# SCH_BSPD_Main.net
KiCad netlist of a schematic drawn in Altium Designer
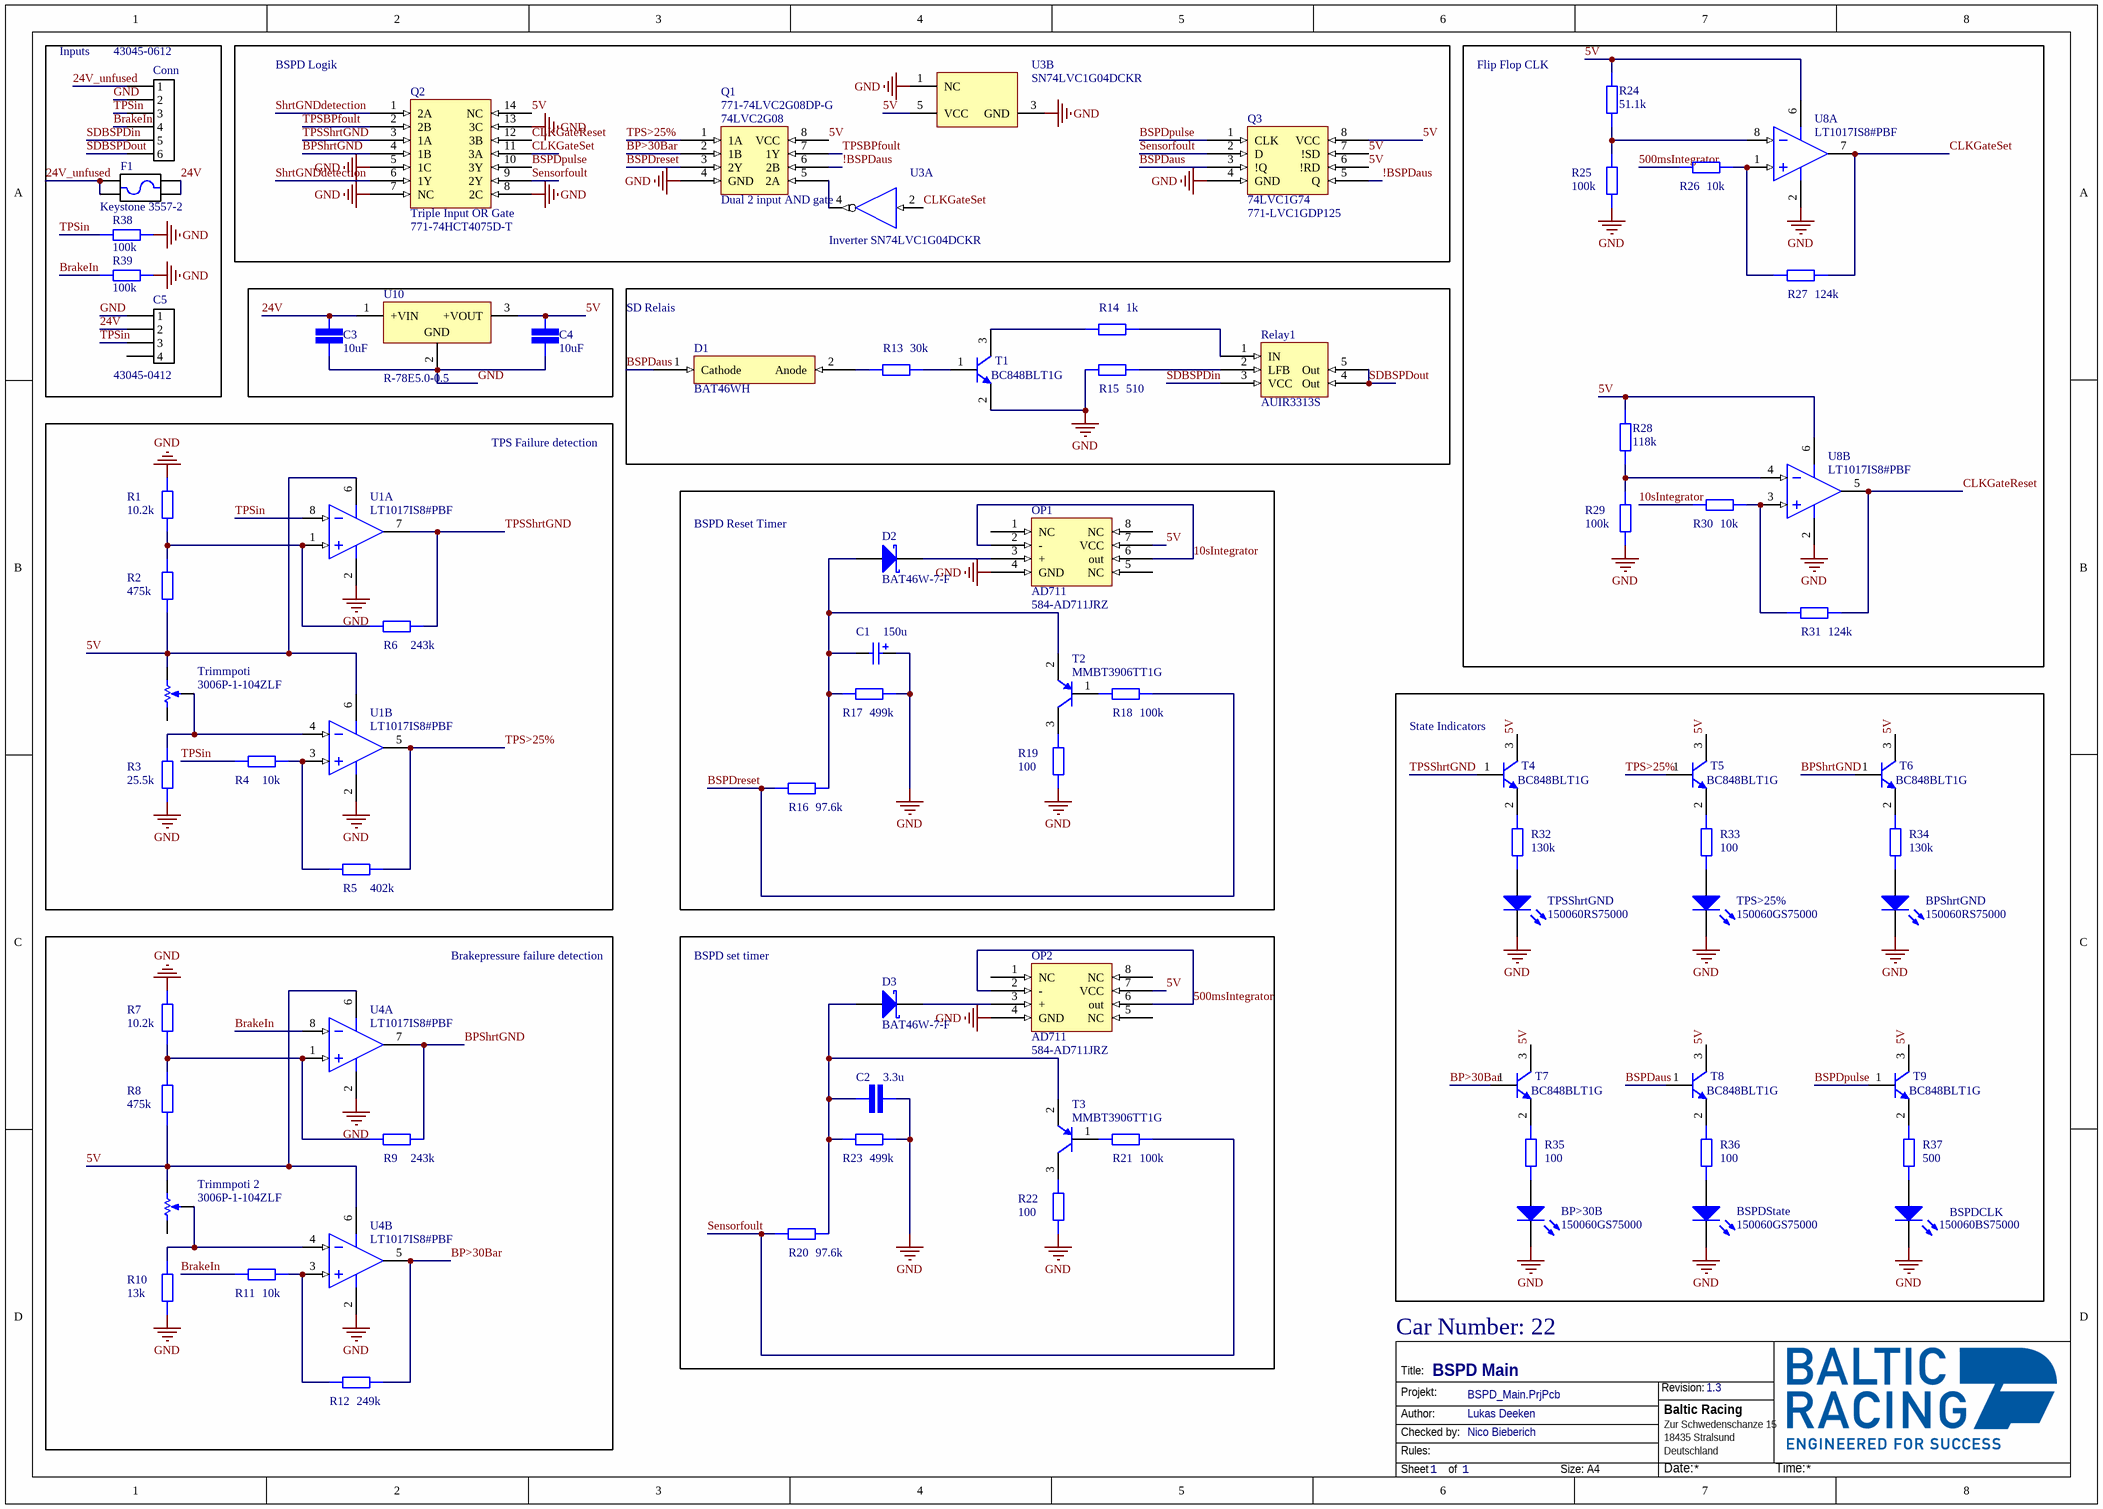
[diagram p0: SCH_BSPD_Main.SchDoc]

(export (version "E")
  (design (tool "Eeschema 10.0.6"))
  (components
    (comp (ref "BP>30B")
      (value "150060GS75000")
      (footprint "0603_A")
      (description "SMD mono-color Chip LED, WL-SMCW, Green")
      (fields (field (name "MANUFACTURER") "Wuerth Elektronik"))
      (libsource (lib "Altium Content Vault") (part "WE-LED_K1A2-2"))
    )
    (comp (ref "BPShrtGND")
      (value "150060RS75000")
      (footprint "0603_A")
      (description "SMD mono-color Chip LED, WL-SMCW, Red")
      (fields (field (name "MANUFACTURER") "Wuerth Elektronik"))
      (libsource (lib "Altium Content Vault") (part "WE-LED_K1A2-2"))
    )
    (comp (ref "BSPDCLK")
      (value "150060BS75000")
      (footprint "0603_A")
      (description "SMD mono-color Chip LED, WL-SMCW, Blue")
      (fields (field (name "MANUFACTURER") "Wuerth Elektronik"))
      (libsource (lib "Altium Content Vault") (part "WE-LED_K1A2-2"))
    )
    (comp (ref "BSPDState")
      (value "150060GS75000")
      (footprint "0603_A")
      (description "SMD mono-color Chip LED, WL-SMCW, Green")
      (fields (field (name "MANUFACTURER") "Wuerth Elektronik"))
      (libsource (lib "Altium Content Vault") (part "WE-LED_K1A2-2"))
    )
    (comp (ref "C1")
      (value "150u")
      (footprint "WCAP-PSLC_10x12.4")
      (description "WCAP-PSLC Aluminum Polymer Capacitors, size Ф10x12.4mm, 25V DC, 150uF")
      (fields (field (name "PART NUMBER") "875075561006") (field (name "PUBLISHER") "Wurth Elektronik"))
      (libsource (lib "ALTIUM-WCAP-PSLC-rev17b") (part "875075561006"))
    )
    (comp (ref "C2")
      (value "3.3u")
      (footprint "CAP 0603/1608")
      (description "Capacitor with multiple Footprints")
      (fields (field (name "VOLTAGE") "6.3V") (field (name "Comment") "SMD Capacitor"))
      (libsource (lib "") (part "SMD Capacitor_1"))
    )
    (comp (ref "C3")
      (value "10uF")
      (footprint "CAP 0805/2012")
      (description "Capacitor with multiple Footprints")
      (fields (field (name "VOLTAGE") "25V") (field (name "Comment") "SMD Capacitor"))
      (libsource (lib "Standardbauteile") (part "SMD Capacitor"))
    )
    (comp (ref "C4")
      (value "10uF")
      (footprint "CAP 0805/2012")
      (description "Capacitor with multiple Footprints")
      (fields (field (name "VOLTAGE") "6.3V") (field (name "Comment") "SMD Capacitor"))
      (libsource (lib "Standardbauteile") (part "SMD Capacitor"))
    )
    (comp (ref "C5")
      (value "43045-0412")
      (footprint "43045-0412")
      (description "Molex Micro-Fit 3.0 4-Pin\r\n600V\r\n8.5A")
      (libsource (lib "Standardbauteile") (part "MicroFit3.0 4-Pin"))
    )
    (comp (ref "Conn")
      (value "43045-0612")
      (footprint "43045-0612")
      (description "Molex Micro-Fit 3.0 6-Pin\r\n600V\r\n8.5A")
      (libsource (lib "Standardbauteile") (part "MicroFit3.0 6-Pin"))
    )
    (comp (ref "D1")
      (value "BAT46WH")
      (footprint "DIOM2715X18N")
      (libsource (lib "Integrated_LibraryLukas") (part "BAT46WH"))
    )
    (comp (ref "D2")
      (value "BAT46W-7-F")
      (footprint "DIOD-SOD-123-2_V")
      (description "Surface Mount Schottky Barrier Diode, 100 V, -55 to 125 degC, 2-Pin SOD123, RoHS, Tape and Reel")
      (fields (field (name "MANUFACTURER") "Diodes Inc"))
      (libsource (lib "Altium Content Vault") (part "DIOD-DSKY-A1K2-2"))
    )
    (comp (ref "D3")
      (value "BAT46W-7-F")
      (footprint "DIOD-SOD-123-2_V")
      (description "Surface Mount Schottky Barrier Diode, 100 V, -55 to 125 degC, 2-Pin SOD123, RoHS, Tape and Reel")
      (fields (field (name "MANUFACTURER") "Diodes Inc"))
      (libsource (lib "Altium Content Vault") (part "DIOD-DSKY-A1K2-2"))
    )
    (comp (ref "F1")
      (value "Keystone 3557-2")
      (footprint "Keystone 3557-2")
      (description "Keystone 3557-2\r\nFuse Holder")
      (libsource (lib "libNico") (part "Keystone 3557-2"))
    )
    (comp (ref "OP1")
      (value "AD711")
      (footprint "SOIC8; SOIC127P600X175-8N")
      (fields (field (name "SUPPLIER PART NUMBER 1") "584-AD711JRZ"))
      (libsource (lib "Integrated_LibraryLukas") (part "AD711"))
    )
    (comp (ref "OP2")
      (value "AD711")
      (footprint "SOIC8; SOIC127P600X175-8N")
      (fields (field (name "SUPPLIER PART NUMBER 1") "584-AD711JRZ"))
      (libsource (lib "Integrated_LibraryLukas") (part "AD711"))
    )
    (comp (ref "Q1")
      (value "Dual 2 input AND gate")
      (footprint "TSSOP8; TSOP65P400X110-8N")
      (fields (field (name "SUPPLIER PART NUMBER 1") "771-74LVC2G08DP-G"))
      (libsource (lib "Integrated_LibraryLukas") (part "74LVC2G08-Q100"))
    )
    (comp (ref "Q2")
      (value "Triple Input OR Gate")
      (footprint "SOIC14; SOIC127P600X175-14N")
      (fields (field (name "SUPPLIER PART NUMBER 1") "771-74HCT4075D-T"))
      (libsource (lib "Integrated_LibraryLukas") (part "74HCT4075D,653"))
    )
    (comp (ref "Q3")
      (value "74LVC1G74")
      (footprint "TSSOP8; TSOP65P400X110-8N")
      (fields (field (name "SUPPLIER PART NUMBER 1") "771-LVC1GDP125"))
      (libsource (lib "Integrated_LibraryLukas") (part "74LVC1G74"))
    )
    (comp (ref "R1")
      (value "10.2k")
      (footprint "STACKPOLE CSR0603")
      (description "Resistor with multiple footprints")
      (fields (field (name "Comment") "SMD Resistor"))
      (libsource (lib "Standardbauteile") (part "SMD Resistor"))
    )
    (comp (ref "R2")
      (value "475k")
      (footprint "STACKPOLE CSR0603")
      (description "Resistor with multiple footprints")
      (fields (field (name "Comment") "SMD Resistor"))
      (libsource (lib "Standardbauteile") (part "SMD Resistor"))
    )
    (comp (ref "R3")
      (value "25.5k")
      (footprint "STACKPOLE CSR0603")
      (description "Resistor with multiple footprints")
      (fields (field (name "Comment") "SMD Resistor"))
      (libsource (lib "Standardbauteile") (part "SMD Resistor"))
    )
    (comp (ref "R4")
      (value "10k")
      (footprint "STACKPOLE CSR0603")
      (description "Resistor with multiple footprints")
      (fields (field (name "Comment") "SMD Resistor"))
      (libsource (lib "Standardbauteile") (part "SMD Resistor"))
    )
    (comp (ref "R5")
      (value "402k")
      (footprint "STACKPOLE CSR0603")
      (description "Resistor with multiple footprints")
      (fields (field (name "Comment") "SMD Resistor"))
      (libsource (lib "Standardbauteile") (part "SMD Resistor"))
    )
    (comp (ref "R6")
      (value "243k")
      (footprint "STACKPOLE CSR0603")
      (description "Resistor with multiple footprints")
      (fields (field (name "Comment") "SMD Resistor"))
      (libsource (lib "Standardbauteile") (part "SMD Resistor"))
    )
    (comp (ref "R7")
      (value "10.2k")
      (footprint "STACKPOLE CSR0603")
      (description "Resistor with multiple footprints")
      (fields (field (name "Comment") "SMD Resistor"))
      (libsource (lib "Standardbauteile") (part "SMD Resistor"))
    )
    (comp (ref "R8")
      (value "475k")
      (footprint "STACKPOLE CSR0603")
      (description "Resistor with multiple footprints")
      (fields (field (name "Comment") "SMD Resistor"))
      (libsource (lib "Standardbauteile") (part "SMD Resistor"))
    )
    (comp (ref "R9")
      (value "243k")
      (footprint "STACKPOLE CSR0603")
      (description "Resistor with multiple footprints")
      (fields (field (name "Comment") "SMD Resistor"))
      (libsource (lib "Standardbauteile") (part "SMD Resistor"))
    )
    (comp (ref "R10")
      (value "13k")
      (footprint "STACKPOLE CSR0603")
      (description "Resistor with multiple footprints")
      (fields (field (name "Comment") "SMD Resistor"))
      (libsource (lib "Standardbauteile") (part "SMD Resistor"))
    )
    (comp (ref "R11")
      (value "10k")
      (footprint "STACKPOLE CSR0603")
      (description "Resistor with multiple footprints")
      (fields (field (name "Comment") "SMD Resistor"))
      (libsource (lib "Standardbauteile") (part "SMD Resistor"))
    )
    (comp (ref "R12")
      (value "249k")
      (footprint "STACKPOLE CSR0603")
      (description "Resistor with multiple footprints")
      (fields (field (name "Comment") "SMD Resistor"))
      (libsource (lib "Standardbauteile") (part "SMD Resistor"))
    )
    (comp (ref "R13")
      (value "30k")
      (footprint "STACKPOLE CSR0603")
      (description "Resistor with multiple footprints")
      (fields (field (name "Comment") "SMD Resistor"))
      (libsource (lib "Standardbauteile") (part "SMD Resistor"))
    )
    (comp (ref "R14")
      (value "1k")
      (footprint "STACKPOLE CSR0805")
      (description "Resistor with multiple footprints")
      (fields (field (name "Comment") "SMD Resistor"))
      (libsource (lib "Standardbauteile") (part "SMD Resistor"))
    )
    (comp (ref "R15")
      (value "510")
      (footprint "STACKPOLE CSR0603")
      (description "Resistor with multiple footprints")
      (fields (field (name "Comment") "SMD Resistor"))
      (libsource (lib "Standardbauteile") (part "SMD Resistor"))
    )
    (comp (ref "R16")
      (value "97.6k")
      (footprint "STACKPOLE CSR0603")
      (description "Resistor with multiple footprints")
      (fields (field (name "Comment") "SMD Resistor"))
      (libsource (lib "Standardbauteile") (part "SMD Resistor"))
    )
    (comp (ref "R17")
      (value "499k")
      (footprint "STACKPOLE CSR0603")
      (description "Resistor with multiple footprints")
      (fields (field (name "Comment") "SMD Resistor"))
      (libsource (lib "Standardbauteile") (part "SMD Resistor"))
    )
    (comp (ref "R18")
      (value "100k")
      (footprint "STACKPOLE CSR0603")
      (description "Resistor with multiple footprints")
      (fields (field (name "Comment") "SMD Resistor"))
      (libsource (lib "Standardbauteile") (part "SMD Resistor"))
    )
    (comp (ref "R19")
      (value "100")
      (footprint "STACKPOLE CSR0805")
      (description "Resistor with multiple footprints")
      (fields (field (name "Comment") "SMD Resistor"))
      (libsource (lib "Standardbauteile") (part "SMD Resistor"))
    )
    (comp (ref "R20")
      (value "97.6k")
      (footprint "STACKPOLE CSR0603")
      (description "Resistor with multiple footprints")
      (fields (field (name "Comment") "SMD Resistor"))
      (libsource (lib "Standardbauteile") (part "SMD Resistor"))
    )
    (comp (ref "R21")
      (value "100k")
      (footprint "STACKPOLE CSR0603")
      (description "Resistor with multiple footprints")
      (fields (field (name "Comment") "SMD Resistor"))
      (libsource (lib "Standardbauteile") (part "SMD Resistor"))
    )
    (comp (ref "R22")
      (value "100")
      (footprint "STACKPOLE CSR0805")
      (description "Resistor with multiple footprints")
      (fields (field (name "Comment") "SMD Resistor"))
      (libsource (lib "Standardbauteile") (part "SMD Resistor"))
    )
    (comp (ref "R23")
      (value "499k")
      (footprint "STACKPOLE CSR0603")
      (description "Resistor with multiple footprints")
      (fields (field (name "Comment") "SMD Resistor"))
      (libsource (lib "Standardbauteile") (part "SMD Resistor"))
    )
    (comp (ref "R24")
      (value "51.1k")
      (footprint "STACKPOLE CSR0603")
      (description "Resistor with multiple footprints")
      (fields (field (name "Comment") "SMD Resistor"))
      (libsource (lib "Standardbauteile") (part "SMD Resistor"))
    )
    (comp (ref "R25")
      (value "100k")
      (footprint "STACKPOLE CSR0603")
      (description "Resistor with multiple footprints")
      (fields (field (name "Comment") "SMD Resistor"))
      (libsource (lib "Standardbauteile") (part "SMD Resistor"))
    )
    (comp (ref "R26")
      (value "10k")
      (footprint "STACKPOLE CSR0603")
      (description "Resistor with multiple footprints")
      (fields (field (name "Comment") "SMD Resistor"))
      (libsource (lib "Standardbauteile") (part "SMD Resistor"))
    )
    (comp (ref "R27")
      (value "124k")
      (footprint "STACKPOLE CSR0603")
      (description "Resistor with multiple footprints")
      (fields (field (name "Comment") "SMD Resistor"))
      (libsource (lib "Standardbauteile") (part "SMD Resistor"))
    )
    (comp (ref "R28")
      (value "118k")
      (footprint "STACKPOLE CSR0603")
      (description "Resistor with multiple footprints")
      (fields (field (name "Comment") "SMD Resistor"))
      (libsource (lib "Standardbauteile") (part "SMD Resistor"))
    )
    (comp (ref "R29")
      (value "100k")
      (footprint "STACKPOLE CSR0603")
      (description "Resistor with multiple footprints")
      (fields (field (name "Comment") "SMD Resistor"))
      (libsource (lib "Standardbauteile") (part "SMD Resistor"))
    )
    (comp (ref "R30")
      (value "10k")
      (footprint "STACKPOLE CSR0603")
      (description "Resistor with multiple footprints")
      (fields (field (name "Comment") "SMD Resistor"))
      (libsource (lib "Standardbauteile") (part "SMD Resistor"))
    )
    (comp (ref "R31")
      (value "124k")
      (footprint "STACKPOLE CSR0603")
      (description "Resistor with multiple footprints")
      (fields (field (name "Comment") "SMD Resistor"))
      (libsource (lib "Standardbauteile") (part "SMD Resistor"))
    )
    (comp (ref "R32")
      (value "130k")
      (footprint "STACKPOLE CSR0603")
      (description "Resistor with multiple footprints")
      (fields (field (name "Comment") "SMD Resistor"))
      (libsource (lib "Standardbauteile") (part "SMD Resistor"))
    )
    (comp (ref "R33")
      (value "100")
      (footprint "STACKPOLE CSR0603")
      (description "Resistor with multiple footprints")
      (fields (field (name "Comment") "SMD Resistor"))
      (libsource (lib "Standardbauteile") (part "SMD Resistor"))
    )
    (comp (ref "R34")
      (value "130k")
      (footprint "STACKPOLE CSR0603")
      (description "Resistor with multiple footprints")
      (fields (field (name "Comment") "SMD Resistor"))
      (libsource (lib "Standardbauteile") (part "SMD Resistor"))
    )
    (comp (ref "R35")
      (value "100")
      (footprint "STACKPOLE CSR0603")
      (description "Resistor with multiple footprints")
      (fields (field (name "Comment") "SMD Resistor"))
      (libsource (lib "Standardbauteile") (part "SMD Resistor"))
    )
    (comp (ref "R36")
      (value "100")
      (footprint "STACKPOLE CSR0603")
      (description "Resistor with multiple footprints")
      (fields (field (name "Comment") "SMD Resistor"))
      (libsource (lib "Standardbauteile") (part "SMD Resistor"))
    )
    (comp (ref "R37")
      (value "500")
      (footprint "STACKPOLE CSR0603")
      (description "Resistor with multiple footprints")
      (fields (field (name "Comment") "SMD Resistor"))
      (libsource (lib "Standardbauteile") (part "SMD Resistor"))
    )
    (comp (ref "R38")
      (value "100k")
      (footprint "STACKPOLE CSR0603")
      (description "Resistor with multiple footprints")
      (fields (field (name "Comment") "SMD Resistor"))
      (libsource (lib "Standardbauteile") (part "SMD Resistor"))
    )
    (comp (ref "R39")
      (value "100k")
      (footprint "STACKPOLE CSR0603")
      (description "Resistor with multiple footprints")
      (fields (field (name "Comment") "SMD Resistor"))
      (libsource (lib "Standardbauteile") (part "SMD Resistor"))
    )
    (comp (ref "Relay1")
      (value "AUIR3313S")
      (footprint "D2PAK5 ;DPAK228P1524X483-5N")
      (libsource (lib "Integrated_LibraryLukas") (part "AUIR3313S"))
    )
    (comp (ref "T1")
      (value "BC848BLT1G")
      (footprint "ONSC-SOT-23-3-318-08_V")
      (description "General Purpose Transistor, NPN Silicon, 3-Pin SOT-23, Pb-Free, Tape and Reel")
      (fields (field (name "MANUFACTURER") "On Semiconductor"))
      (libsource (lib "Altium Content Vault") (part "ONSC-NPN-B1E2C3-3"))
    )
    (comp (ref "T2")
      (value "MMBT3906TT1G")
      (footprint "ONSC-SC-75-3-463-01_V")
      (description "General Purpose Transistor, PNP Silicon, 3-Pin SC-75, Pb-Free, Tape and Reel")
      (fields (field (name "MANUFACTURER") "On Semiconductor"))
      (libsource (lib "Altium Content Vault") (part "ONSC-PNP-B1E2C3-3"))
    )
    (comp (ref "T3")
      (value "MMBT3906TT1G")
      (footprint "ONSC-SC-75-3-463-01_V")
      (description "General Purpose Transistor, PNP Silicon, 3-Pin SC-75, Pb-Free, Tape and Reel")
      (fields (field (name "MANUFACTURER") "On Semiconductor"))
      (libsource (lib "Altium Content Vault") (part "ONSC-PNP-B1E2C3-3"))
    )
    (comp (ref "T4")
      (value "BC848BLT1G")
      (footprint "ONSC-SOT-23-3-318-08_V")
      (description "General Purpose Transistor, NPN Silicon, 3-Pin SOT-23, Pb-Free, Tape and Reel")
      (fields (field (name "MANUFACTURER") "On Semiconductor"))
      (libsource (lib "Altium Content Vault") (part "ONSC-NPN-B1E2C3-3"))
    )
    (comp (ref "T5")
      (value "BC848BLT1G")
      (footprint "ONSC-SOT-23-3-318-08_V")
      (description "General Purpose Transistor, NPN Silicon, 3-Pin SOT-23, Pb-Free, Tape and Reel")
      (fields (field (name "MANUFACTURER") "On Semiconductor"))
      (libsource (lib "Altium Content Vault") (part "ONSC-NPN-B1E2C3-3"))
    )
    (comp (ref "T6")
      (value "BC848BLT1G")
      (footprint "ONSC-SOT-23-3-318-08_V")
      (description "General Purpose Transistor, NPN Silicon, 3-Pin SOT-23, Pb-Free, Tape and Reel")
      (fields (field (name "MANUFACTURER") "On Semiconductor"))
      (libsource (lib "Altium Content Vault") (part "ONSC-NPN-B1E2C3-3"))
    )
    (comp (ref "T7")
      (value "BC848BLT1G")
      (footprint "ONSC-SOT-23-3-318-08_V")
      (description "General Purpose Transistor, NPN Silicon, 3-Pin SOT-23, Pb-Free, Tape and Reel")
      (fields (field (name "MANUFACTURER") "On Semiconductor"))
      (libsource (lib "Altium Content Vault") (part "ONSC-NPN-B1E2C3-3"))
    )
    (comp (ref "T8")
      (value "BC848BLT1G")
      (footprint "ONSC-SOT-23-3-318-08_V")
      (description "General Purpose Transistor, NPN Silicon, 3-Pin SOT-23, Pb-Free, Tape and Reel")
      (fields (field (name "MANUFACTURER") "On Semiconductor"))
      (libsource (lib "Altium Content Vault") (part "ONSC-NPN-B1E2C3-3"))
    )
    (comp (ref "T9")
      (value "BC848BLT1G")
      (footprint "ONSC-SOT-23-3-318-08_V")
      (description "General Purpose Transistor, NPN Silicon, 3-Pin SOT-23, Pb-Free, Tape and Reel")
      (fields (field (name "MANUFACTURER") "On Semiconductor"))
      (libsource (lib "Altium Content Vault") (part "ONSC-NPN-B1E2C3-3"))
    )
    (comp (ref "TPS>25%")
      (value "150060GS75000")
      (footprint "0603_A")
      (description "SMD mono-color Chip LED, WL-SMCW, Green")
      (fields (field (name "MANUFACTURER") "Wuerth Elektronik"))
      (libsource (lib "Altium Content Vault") (part "WE-LED_K1A2-2"))
    )
    (comp (ref "TPSShrtGND")
      (value "150060RS75000")
      (footprint "0603_A")
      (description "SMD mono-color Chip LED, WL-SMCW, Red")
      (fields (field (name "MANUFACTURER") "Wuerth Elektronik"))
      (libsource (lib "Altium Content Vault") (part "WE-LED_K1A2-2"))
    )
    (comp (ref "Trimmpoti")
      (value "3006P-1-104ZLF")
      (footprint "BOUR-3006P-3_V")
      (description "Trimming Potentiometer, 100K Ohm +/- 10%, -55 to 125 degC, 3-Pin 19.05 x 4.83 x 6.6 mm THD, RoHS")
      (fields (field (name "MANUFACTURER") "Bourns"))
      (libsource (lib "Altium Content Vault") (part "BOUR-3006P-3"))
    )
    (comp (ref "Trimmpoti 2")
      (value "3006P-1-104ZLF")
      (footprint "BOUR-3006P-3_V")
      (description "Trimming Potentiometer, 100K Ohm +/- 10%, -55 to 125 degC, 3-Pin 19.05 x 4.83 x 6.6 mm THD, RoHS")
      (fields (field (name "MANUFACTURER") "Bourns"))
      (libsource (lib "Altium Content Vault") (part "BOUR-3006P-3"))
    )
    (comp (ref "U1")
      (value "LT1017IS8#PBF")
      (footprint "LT-S8_N")
      (description "Micropower Comparator, 2 Channels, 1.2 to 40 V, -40 to +85 degC, 8-pin SOP (S8)")
      (fields (field (name "MANUFACTURER") "Linear Technology") (field (name "GENERIC PART NUMBER") "LT1017"))
      (libsource (lib "Altium Content Vault") (part "LT-LT1017-SO8"))
    )
    (comp (ref "U3")
      (value "Inverter SN74LVC1G04DCKR")
      (footprint "DCK0005A_N")
      (description "Single Inverter, DCK0005A, LARGE T&R")
      (fields
        (field (name "GENERIC PART NUMBER") "SN74LVC1G04")
        (field (name "MANUFACTURER") "Texas Instruments")
      )
      (libsource (lib "Altium Content Vault") (part "TI-SN74XXX1XX4-XX-5"))
    )
    (comp (ref "U4")
      (value "LT1017IS8#PBF")
      (footprint "LT-S8_N")
      (description "Micropower Comparator, 2 Channels, 1.2 to 40 V, -40 to +85 degC, 8-pin SOP (S8)")
      (fields (field (name "MANUFACTURER") "Linear Technology") (field (name "GENERIC PART NUMBER") "LT1017"))
      (libsource (lib "Altium Content Vault") (part "LT-LT1017-SO8"))
    )
    (comp (ref "U8")
      (value "LT1017IS8#PBF")
      (footprint "LT-S8_N")
      (description "Micropower Comparator, 2 Channels, 1.2 to 40 V, -40 to +85 degC, 8-pin SOP (S8)")
      (fields (field (name "MANUFACTURER") "Linear Technology") (field (name "GENERIC PART NUMBER") "LT1017"))
      (libsource (lib "Altium Content Vault") (part "LT-LT1017-SO8"))
    )
    (comp (ref "U10")
      (value "R-78E5.0-0.5")
      (footprint "REPO-R-78E-0.5-3_V")
      (description "DC/DC-Converter, 5 V Single Output, 500 mA, -40 to 85 degC, 3-Pin THD, RoHS, Tube")
      (fields (field (name "MANUFACTURER") "Recom Power"))
      (libsource (lib "Altium Content Vault") (part "REPO-R-78XX-3"))
    )
  )
  (nets
    (net (code "1") (name "/!BSPDaus") (class "Default")
      (node (ref "Q1") (pin "6") (pinfunction "2B_6") (pintype "input"))
      (node (ref "Q3") (pin "5") (pinfunction "Q_5") (pintype "input"))
    )
    (net (code "2") (name "/5V") (class "Default")
      (node (ref "C4") (pin "2") (pinfunction "2_2") (pintype "passive"))
      (node (ref "OP1") (pin "7") (pinfunction "VCC_7") (pintype "input"))
      (node (ref "OP2") (pin "7") (pinfunction "VCC_7") (pintype "input"))
      (node (ref "Q1") (pin "8") (pinfunction "VCC_8") (pintype "input"))
      (node (ref "Q2") (pin "14") (pinfunction "NC_14") (pintype "input"))
      (node (ref "Q3") (pin "6") (pinfunction "!RD_6") (pintype "input"))
      (node (ref "Q3") (pin "7") (pinfunction "!SD_7") (pintype "input"))
      (node (ref "Q3") (pin "8") (pinfunction "VCC_8") (pintype "input"))
      (node (ref "R2") (pin "2") (pinfunction "2_2") (pintype "passive"))
      (node (ref "R24") (pin "2") (pinfunction "2_2") (pintype "passive"))
      (node (ref "R28") (pin "2") (pinfunction "2_2") (pintype "passive"))
      (node (ref "R8") (pin "2") (pinfunction "2_2") (pintype "passive"))
      (node (ref "T4") (pin "3") (pinfunction "C_3") (pintype "passive"))
      (node (ref "T5") (pin "3") (pinfunction "C_3") (pintype "passive"))
      (node (ref "T6") (pin "3") (pinfunction "C_3") (pintype "passive"))
      (node (ref "T7") (pin "3") (pinfunction "C_3") (pintype "passive"))
      (node (ref "T8") (pin "3") (pinfunction "C_3") (pintype "passive"))
      (node (ref "T9") (pin "3") (pinfunction "C_3") (pintype "passive"))
      (node (ref "Trimmpoti") (pin "1") (pinfunction "CCW_1") (pintype "passive"))
      (node (ref "Trimmpoti 2") (pin "1") (pinfunction "CCW_1") (pintype "passive"))
      (node (ref "U1") (pin "6") (pinfunction "V+_6") (pintype "power_in"))
      (node (ref "U10") (pin "3") (pinfunction "+VOUT_3") (pintype "power_in"))
      (node (ref "U3") (pin "5") (pinfunction "VCC_5") (pintype "power_in"))
      (node (ref "U4") (pin "6") (pinfunction "V+_6") (pintype "power_in"))
      (node (ref "U8") (pin "6") (pinfunction "V+_6") (pintype "power_in"))
    )
    (net (code "3") (name "/10sIntegrator") (class "Default")
      (node (ref "OP1") (pin "2") (pinfunction "-_2") (pintype "input"))
      (node (ref "OP1") (pin "6") (pinfunction "out_6") (pintype "input"))
      (node (ref "R30") (pin "2") (pinfunction "2_2") (pintype "passive"))
    )
    (net (code "4") (name "/24V") (class "Default")
      (node (ref "C3") (pin "2") (pinfunction "2_2") (pintype "passive"))
      (node (ref "C5") (pin "2") (pinfunction "2_2") (pintype "passive"))
      (node (ref "F1") (pin "O1") (pinfunction "O1_O1") (pintype "passive"))
      (node (ref "F1") (pin "O2") (pinfunction "O2_O2") (pintype "passive"))
      (node (ref "U10") (pin "1") (pinfunction "+VIN_1") (pintype "power_in"))
    )
    (net (code "5") (name "/24V_unfused") (class "Default")
      (node (ref "Conn") (pin "1") (pinfunction "1_1") (pintype "passive"))
      (node (ref "F1") (pin "I1") (pinfunction "I1_I1") (pintype "passive"))
      (node (ref "F1") (pin "I2") (pinfunction "I2_I2") (pintype "passive"))
    )
    (net (code "6") (name "/500msIntegrator") (class "Default")
      (node (ref "OP2") (pin "2") (pinfunction "-_2") (pintype "input"))
      (node (ref "OP2") (pin "6") (pinfunction "out_6") (pintype "input"))
      (node (ref "R26") (pin "2") (pinfunction "2_2") (pintype "passive"))
    )
    (net (code "7") (name "/BP>30Bar") (class "Default")
      (node (ref "Q1") (pin "2") (pinfunction "1B_2") (pintype "input"))
      (node (ref "R12") (pin "2") (pinfunction "2_2") (pintype "passive"))
      (node (ref "T7") (pin "1") (pinfunction "B_1") (pintype "passive"))
      (node (ref "U4") (pin "5") (pinfunction "OUT_B_5") (pintype "open_collector"))
    )
    (net (code "8") (name "/BPShrtGND") (class "Default")
      (node (ref "Q2") (pin "4") (pinfunction "1B_4") (pintype "input"))
      (node (ref "R9") (pin "1") (pinfunction "1_1") (pintype "passive"))
      (node (ref "T6") (pin "1") (pinfunction "B_1") (pintype "passive"))
      (node (ref "U4") (pin "7") (pinfunction "OUT_A_7") (pintype "open_collector"))
    )
    (net (code "9") (name "/BSPDaus") (class "Default")
      (node (ref "D1") (pin "1") (pinfunction "Cathode_1") (pintype "input"))
      (node (ref "Q3") (pin "3") (pinfunction "!Q_3") (pintype "input"))
      (node (ref "T8") (pin "1") (pinfunction "B_1") (pintype "passive"))
    )
    (net (code "10") (name "/BSPDpulse") (class "Default")
      (node (ref "Q2") (pin "10") (pinfunction "3Y_10") (pintype "input"))
      (node (ref "Q3") (pin "1") (pinfunction "CLK_1") (pintype "input"))
      (node (ref "T9") (pin "1") (pinfunction "B_1") (pintype "passive"))
    )
    (net (code "11") (name "/BSPDreset") (class "Default")
      (node (ref "Q1") (pin "3") (pinfunction "2Y_3") (pintype "input"))
      (node (ref "R16") (pin "1") (pinfunction "1_1") (pintype "passive"))
      (node (ref "R18") (pin "2") (pinfunction "2_2") (pintype "passive"))
    )
    (net (code "12") (name "/BrakeIn") (class "Default")
      (node (ref "Conn") (pin "4") (pinfunction "4_4") (pintype "passive"))
      (node (ref "R11") (pin "2") (pinfunction "2_2") (pintype "passive"))
      (node (ref "R39") (pin "1") (pinfunction "1_1") (pintype "passive"))
      (node (ref "U4") (pin "8") (pinfunction "-IN_A_8") (pintype "input"))
    )
    (net (code "13") (name "/CLKGateReset") (class "Default")
      (node (ref "Q2") (pin "12") (pinfunction "3B_12") (pintype "input"))
      (node (ref "R31") (pin "2") (pinfunction "2_2") (pintype "passive"))
      (node (ref "U8") (pin "5") (pinfunction "OUT_B_5") (pintype "open_collector"))
    )
    (net (code "14") (name "/CLKGateSet") (class "Default")
      (node (ref "Q2") (pin "11") (pinfunction "3A_11") (pintype "input"))
      (node (ref "R27") (pin "2") (pinfunction "2_2") (pintype "passive"))
      (node (ref "U3") (pin "2") (pinfunction "A_2") (pintype "input"))
      (node (ref "U8") (pin "7") (pinfunction "OUT_A_7") (pintype "open_collector"))
    )
    (net (code "15") (name "/SDBSPDin") (class "Default")
      (node (ref "Conn") (pin "5") (pinfunction "5_5") (pintype "passive"))
      (node (ref "Relay1") (pin "3") (pinfunction "VCC_3") (pintype "input"))
    )
    (net (code "16") (name "/SDBSPDout") (class "Default")
      (node (ref "Conn") (pin "6") (pinfunction "6_6") (pintype "passive"))
      (node (ref "Relay1") (pin "4") (pinfunction "Out_4") (pintype "input"))
      (node (ref "Relay1") (pin "5") (pinfunction "Out_5") (pintype "input"))
    )
    (net (code "17") (name "/Sensorfoult") (class "Default")
      (node (ref "Q2") (pin "9") (pinfunction "2Y_9") (pintype "input"))
      (node (ref "Q3") (pin "2") (pinfunction "D_2") (pintype "input"))
      (node (ref "R20") (pin "1") (pinfunction "1_1") (pintype "passive"))
      (node (ref "R21") (pin "2") (pinfunction "2_2") (pintype "passive"))
    )
    (net (code "18") (name "/ShrtGNDdetection") (class "Default")
      (node (ref "Q2") (pin "1") (pinfunction "2A_1") (pintype "input"))
      (node (ref "Q2") (pin "6") (pinfunction "1Y_6") (pintype "input"))
    )
    (net (code "19") (name "/TPS>25%") (class "Default")
      (node (ref "Q1") (pin "1") (pinfunction "1A_1") (pintype "input"))
      (node (ref "R5") (pin "1") (pinfunction "1_1") (pintype "passive"))
      (node (ref "T5") (pin "1") (pinfunction "B_1") (pintype "passive"))
      (node (ref "U1") (pin "5") (pinfunction "OUT_B_5") (pintype "open_collector"))
    )
    (net (code "20") (name "/TPSBPfoult") (class "Default")
      (node (ref "Q1") (pin "7") (pinfunction "1Y_7") (pintype "input"))
      (node (ref "Q2") (pin "2") (pinfunction "2B_2") (pintype "input"))
    )
    (net (code "21") (name "/TPSShrtGND") (class "Default")
      (node (ref "Q2") (pin "3") (pinfunction "1A_3") (pintype "input"))
      (node (ref "R6") (pin "1") (pinfunction "1_1") (pintype "passive"))
      (node (ref "T4") (pin "1") (pinfunction "B_1") (pintype "passive"))
      (node (ref "U1") (pin "7") (pinfunction "OUT_A_7") (pintype "open_collector"))
    )
    (net (code "22") (name "/TPSin") (class "Default")
      (node (ref "C5") (pin "3") (pinfunction "3_3") (pintype "passive"))
      (node (ref "Conn") (pin "3") (pinfunction "3_3") (pintype "passive"))
      (node (ref "R38") (pin "1") (pinfunction "1_1") (pintype "passive"))
      (node (ref "R4") (pin "2") (pinfunction "2_2") (pintype "passive"))
      (node (ref "U1") (pin "8") (pinfunction "-IN_A_8") (pintype "input"))
    )
    (net (code "23") (name "GND") (class "Default")
      (node (ref "BP>30B") (pin "1") (pinfunction "K_1") (pintype "passive"))
      (node (ref "BPShrtGND") (pin "1") (pinfunction "K_1") (pintype "passive"))
      (node (ref "BSPDCLK") (pin "1") (pinfunction "K_1") (pintype "passive"))
      (node (ref "BSPDState") (pin "1") (pinfunction "K_1") (pintype "passive"))
      (node (ref "C1") (pin "1") (pinfunction "P_1") (pintype "passive"))
      (node (ref "C2") (pin "1") (pinfunction "1_1") (pintype "passive"))
      (node (ref "C3") (pin "1") (pinfunction "1_1") (pintype "passive"))
      (node (ref "C4") (pin "1") (pinfunction "1_1") (pintype "passive"))
      (node (ref "C5") (pin "1") (pinfunction "1_1") (pintype "passive"))
      (node (ref "Conn") (pin "2") (pinfunction "2_2") (pintype "passive"))
      (node (ref "OP1") (pin "4") (pinfunction "GND_4") (pintype "input"))
      (node (ref "OP2") (pin "4") (pinfunction "GND_4") (pintype "input"))
      (node (ref "Q1") (pin "4") (pinfunction "GND_4") (pintype "input"))
      (node (ref "Q2") (pin "13") (pinfunction "3C_13") (pintype "input"))
      (node (ref "Q2") (pin "5") (pinfunction "1C_5") (pintype "input"))
      (node (ref "Q2") (pin "7") (pinfunction "NC_7") (pintype "input"))
      (node (ref "Q2") (pin "8") (pinfunction "2C_8") (pintype "input"))
      (node (ref "Q3") (pin "4") (pinfunction "GND_4") (pintype "input"))
      (node (ref "R1") (pin "1") (pinfunction "1_1") (pintype "passive"))
      (node (ref "R10") (pin "2") (pinfunction "2_2") (pintype "passive"))
      (node (ref "R15") (pin "1") (pinfunction "1_1") (pintype "passive"))
      (node (ref "R17") (pin "2") (pinfunction "2_2") (pintype "passive"))
      (node (ref "R19") (pin "1") (pinfunction "1_1") (pintype "passive"))
      (node (ref "R22") (pin "1") (pinfunction "1_1") (pintype "passive"))
      (node (ref "R23") (pin "2") (pinfunction "2_2") (pintype "passive"))
      (node (ref "R25") (pin "2") (pinfunction "2_2") (pintype "passive"))
      (node (ref "R29") (pin "2") (pinfunction "2_2") (pintype "passive"))
      (node (ref "R3") (pin "2") (pinfunction "2_2") (pintype "passive"))
      (node (ref "R38") (pin "2") (pinfunction "2_2") (pintype "passive"))
      (node (ref "R39") (pin "2") (pinfunction "2_2") (pintype "passive"))
      (node (ref "R7") (pin "1") (pinfunction "1_1") (pintype "passive"))
      (node (ref "T1") (pin "2") (pinfunction "E_2") (pintype "passive"))
      (node (ref "TPS>25%") (pin "1") (pinfunction "K_1") (pintype "passive"))
      (node (ref "TPSShrtGND") (pin "1") (pinfunction "K_1") (pintype "passive"))
      (node (ref "U1") (pin "2") (pinfunction "V-_2") (pintype "power_in"))
      (node (ref "U10") (pin "2") (pinfunction "GND_2") (pintype "power_in"))
      (node (ref "U3") (pin "1") (pinfunction "NC_1") (pintype "passive"))
      (node (ref "U3") (pin "3") (pinfunction "GND_3") (pintype "power_in"))
      (node (ref "U4") (pin "2") (pinfunction "V-_2") (pintype "power_in"))
      (node (ref "U8") (pin "2") (pinfunction "V-_2") (pintype "power_in"))
    )
    (net (code "24") (name "Net-(BP>30B-A)") (class "Default")
      (node (ref "BP>30B") (pin "2") (pinfunction "A_2") (pintype "passive"))
      (node (ref "R35") (pin "1") (pinfunction "1_1") (pintype "passive"))
    )
    (net (code "25") (name "Net-(BPShrtGND-A)") (class "Default")
      (node (ref "BPShrtGND") (pin "2") (pinfunction "A_2") (pintype "passive"))
      (node (ref "R34") (pin "1") (pinfunction "1_1") (pintype "passive"))
    )
    (net (code "26") (name "Net-(BSPDCLK-A)") (class "Default")
      (node (ref "BSPDCLK") (pin "2") (pinfunction "A_2") (pintype "passive"))
      (node (ref "R37") (pin "1") (pinfunction "1_1") (pintype "passive"))
    )
    (net (code "27") (name "Net-(BSPDState-A)") (class "Default")
      (node (ref "BSPDState") (pin "2") (pinfunction "A_2") (pintype "passive"))
      (node (ref "R36") (pin "1") (pinfunction "1_1") (pintype "passive"))
    )
    (net (code "28") (name "Net-(C1-N)") (class "Default")
      (node (ref "C1") (pin "2") (pinfunction "N_2") (pintype "passive"))
      (node (ref "D2") (pin "1") (pinfunction "A_1") (pintype "passive"))
      (node (ref "R16") (pin "2") (pinfunction "2_2") (pintype "passive"))
      (node (ref "R17") (pin "1") (pinfunction "1_1") (pintype "passive"))
      (node (ref "T2") (pin "2") (pinfunction "E_2") (pintype "passive"))
    )
    (net (code "29") (name "Net-(D1-Anode)") (class "Default")
      (node (ref "D1") (pin "2") (pinfunction "Anode_2") (pintype "input"))
      (node (ref "R13") (pin "1") (pinfunction "1_1") (pintype "passive"))
    )
    (net (code "30") (name "Net-(D2-K)") (class "Default")
      (node (ref "D2") (pin "2") (pinfunction "K_2") (pintype "passive"))
      (node (ref "OP1") (pin "3") (pinfunction "+_3") (pintype "input"))
    )
    (net (code "31") (name "Net-(D3-A)") (class "Default")
      (node (ref "C2") (pin "2") (pinfunction "2_2") (pintype "passive"))
      (node (ref "D3") (pin "1") (pinfunction "A_1") (pintype "passive"))
      (node (ref "R20") (pin "2") (pinfunction "2_2") (pintype "passive"))
      (node (ref "R23") (pin "1") (pinfunction "1_1") (pintype "passive"))
      (node (ref "T3") (pin "2") (pinfunction "E_2") (pintype "passive"))
    )
    (net (code "32") (name "Net-(D3-K)") (class "Default")
      (node (ref "D3") (pin "2") (pinfunction "K_2") (pintype "passive"))
      (node (ref "OP2") (pin "3") (pinfunction "+_3") (pintype "input"))
    )
    (net (code "33") (name "Net-(Q1-2A)") (class "Default")
      (node (ref "Q1") (pin "5") (pinfunction "2A_5") (pintype "input"))
      (node (ref "U3") (pin "4") (pinfunction "Y_4") (pintype "output"))
    )
    (net (code "34") (name "Net-(Relay1-IN)") (class "Default")
      (node (ref "R14") (pin "2") (pinfunction "2_2") (pintype "passive"))
      (node (ref "Relay1") (pin "1") (pinfunction "IN_1") (pintype "input"))
    )
    (net (code "35") (name "Net-(Relay1-LFB)") (class "Default")
      (node (ref "R15") (pin "2") (pinfunction "2_2") (pintype "passive"))
      (node (ref "Relay1") (pin "2") (pinfunction "LFB_2") (pintype "input"))
    )
    (net (code "36") (name "Net-(T1-B)") (class "Default")
      (node (ref "R13") (pin "2") (pinfunction "2_2") (pintype "passive"))
      (node (ref "T1") (pin "1") (pinfunction "B_1") (pintype "passive"))
    )
    (net (code "37") (name "Net-(T1-C)") (class "Default")
      (node (ref "R14") (pin "1") (pinfunction "1_1") (pintype "passive"))
      (node (ref "T1") (pin "3") (pinfunction "C_3") (pintype "passive"))
    )
    (net (code "38") (name "Net-(T2-B)") (class "Default")
      (node (ref "R18") (pin "1") (pinfunction "1_1") (pintype "passive"))
      (node (ref "T2") (pin "1") (pinfunction "B_1") (pintype "passive"))
    )
    (net (code "39") (name "Net-(T2-C)") (class "Default")
      (node (ref "R19") (pin "2") (pinfunction "2_2") (pintype "passive"))
      (node (ref "T2") (pin "3") (pinfunction "C_3") (pintype "passive"))
    )
    (net (code "40") (name "Net-(T3-B)") (class "Default")
      (node (ref "R21") (pin "1") (pinfunction "1_1") (pintype "passive"))
      (node (ref "T3") (pin "1") (pinfunction "B_1") (pintype "passive"))
    )
    (net (code "41") (name "Net-(T3-C)") (class "Default")
      (node (ref "R22") (pin "2") (pinfunction "2_2") (pintype "passive"))
      (node (ref "T3") (pin "3") (pinfunction "C_3") (pintype "passive"))
    )
    (net (code "42") (name "Net-(T4-E)") (class "Default")
      (node (ref "R32") (pin "2") (pinfunction "2_2") (pintype "passive"))
      (node (ref "T4") (pin "2") (pinfunction "E_2") (pintype "passive"))
    )
    (net (code "43") (name "Net-(T5-E)") (class "Default")
      (node (ref "R33") (pin "2") (pinfunction "2_2") (pintype "passive"))
      (node (ref "T5") (pin "2") (pinfunction "E_2") (pintype "passive"))
    )
    (net (code "44") (name "Net-(T6-E)") (class "Default")
      (node (ref "R34") (pin "2") (pinfunction "2_2") (pintype "passive"))
      (node (ref "T6") (pin "2") (pinfunction "E_2") (pintype "passive"))
    )
    (net (code "45") (name "Net-(T7-E)") (class "Default")
      (node (ref "R35") (pin "2") (pinfunction "2_2") (pintype "passive"))
      (node (ref "T7") (pin "2") (pinfunction "E_2") (pintype "passive"))
    )
    (net (code "46") (name "Net-(T8-E)") (class "Default")
      (node (ref "R36") (pin "2") (pinfunction "2_2") (pintype "passive"))
      (node (ref "T8") (pin "2") (pinfunction "E_2") (pintype "passive"))
    )
    (net (code "47") (name "Net-(T9-E)") (class "Default")
      (node (ref "R37") (pin "2") (pinfunction "2_2") (pintype "passive"))
      (node (ref "T9") (pin "2") (pinfunction "E_2") (pintype "passive"))
    )
    (net (code "48") (name "Net-(TPS>25%-A)") (class "Default")
      (node (ref "R33") (pin "1") (pinfunction "1_1") (pintype "passive"))
      (node (ref "TPS>25%") (pin "2") (pinfunction "A_2") (pintype "passive"))
    )
    (net (code "49") (name "Net-(TPSShrtGND-A)") (class "Default")
      (node (ref "R32") (pin "1") (pinfunction "1_1") (pintype "passive"))
      (node (ref "TPSShrtGND") (pin "2") (pinfunction "A_2") (pintype "passive"))
    )
    (net (code "50") (name "Net-(Trimmpoti 2-WIPER)") (class "Default")
      (node (ref "R10") (pin "1") (pinfunction "1_1") (pintype "passive"))
      (node (ref "Trimmpoti 2") (pin "2") (pinfunction "WIPER_2") (pintype "passive"))
      (node (ref "U4") (pin "4") (pinfunction "-IN_B_4") (pintype "input"))
    )
    (net (code "51") (name "Net-(Trimmpoti-WIPER)") (class "Default")
      (node (ref "R3") (pin "1") (pinfunction "1_1") (pintype "passive"))
      (node (ref "Trimmpoti") (pin "2") (pinfunction "WIPER_2") (pintype "passive"))
      (node (ref "U1") (pin "4") (pinfunction "-IN_B_4") (pintype "input"))
    )
    (net (code "52") (name "Net-(U1A-+IN_A)") (class "Default")
      (node (ref "R1") (pin "2") (pinfunction "2_2") (pintype "passive"))
      (node (ref "R2") (pin "1") (pinfunction "1_1") (pintype "passive"))
      (node (ref "R6") (pin "2") (pinfunction "2_2") (pintype "passive"))
      (node (ref "U1") (pin "1") (pinfunction "+IN_A_1") (pintype "input"))
    )
    (net (code "53") (name "Net-(U1B-+IN_B)") (class "Default")
      (node (ref "R4") (pin "1") (pinfunction "1_1") (pintype "passive"))
      (node (ref "R5") (pin "2") (pinfunction "2_2") (pintype "passive"))
      (node (ref "U1") (pin "3") (pinfunction "+IN_B_3") (pintype "input"))
    )
    (net (code "54") (name "Net-(U4A-+IN_A)") (class "Default")
      (node (ref "R7") (pin "2") (pinfunction "2_2") (pintype "passive"))
      (node (ref "R8") (pin "1") (pinfunction "1_1") (pintype "passive"))
      (node (ref "R9") (pin "2") (pinfunction "2_2") (pintype "passive"))
      (node (ref "U4") (pin "1") (pinfunction "+IN_A_1") (pintype "input"))
    )
    (net (code "55") (name "Net-(U4B-+IN_B)") (class "Default")
      (node (ref "R11") (pin "1") (pinfunction "1_1") (pintype "passive"))
      (node (ref "R12") (pin "1") (pinfunction "1_1") (pintype "passive"))
      (node (ref "U4") (pin "3") (pinfunction "+IN_B_3") (pintype "input"))
    )
    (net (code "56") (name "Net-(U8A-+IN_A)") (class "Default")
      (node (ref "R26") (pin "1") (pinfunction "1_1") (pintype "passive"))
      (node (ref "R27") (pin "1") (pinfunction "1_1") (pintype "passive"))
      (node (ref "U8") (pin "1") (pinfunction "+IN_A_1") (pintype "input"))
    )
    (net (code "57") (name "Net-(U8A--IN_A)") (class "Default")
      (node (ref "R24") (pin "1") (pinfunction "1_1") (pintype "passive"))
      (node (ref "R25") (pin "1") (pinfunction "1_1") (pintype "passive"))
      (node (ref "U8") (pin "8") (pinfunction "-IN_A_8") (pintype "input"))
    )
    (net (code "58") (name "Net-(U8B-+IN_B)") (class "Default")
      (node (ref "R30") (pin "1") (pinfunction "1_1") (pintype "passive"))
      (node (ref "R31") (pin "1") (pinfunction "1_1") (pintype "passive"))
      (node (ref "U8") (pin "3") (pinfunction "+IN_B_3") (pintype "input"))
    )
    (net (code "59") (name "Net-(U8B--IN_B)") (class "Default")
      (node (ref "R28") (pin "1") (pinfunction "1_1") (pintype "passive"))
      (node (ref "R29") (pin "1") (pinfunction "1_1") (pintype "passive"))
      (node (ref "U8") (pin "4") (pinfunction "-IN_B_4") (pintype "input"))
    )
    (net (code "60") (name "unconnected-(C5-Pad4)") (class "Default")
      (node (ref "C5") (pin "4") (pinfunction "4_4") (pintype "passive"))
    )
    (net (code "61") (name "unconnected-(OP1-NC-Pad1)") (class "Default")
      (node (ref "OP1") (pin "1") (pinfunction "NC_1") (pintype "input"))
    )
    (net (code "62") (name "unconnected-(OP1-NC-Pad5)") (class "Default")
      (node (ref "OP1") (pin "5") (pinfunction "NC_5") (pintype "input"))
    )
    (net (code "63") (name "unconnected-(OP1-NC-Pad8)") (class "Default")
      (node (ref "OP1") (pin "8") (pinfunction "NC_8") (pintype "input"))
    )
    (net (code "64") (name "unconnected-(OP2-NC-Pad1)") (class "Default")
      (node (ref "OP2") (pin "1") (pinfunction "NC_1") (pintype "input"))
    )
    (net (code "65") (name "unconnected-(OP2-NC-Pad5)") (class "Default")
      (node (ref "OP2") (pin "5") (pinfunction "NC_5") (pintype "input"))
    )
    (net (code "66") (name "unconnected-(OP2-NC-Pad8)") (class "Default")
      (node (ref "OP2") (pin "8") (pinfunction "NC_8") (pintype "input"))
    )
    (net (code "67") (name "unconnected-(Trimmpoti 2-CW-Pad3)") (class "Default")
      (node (ref "Trimmpoti 2") (pin "3") (pinfunction "CW_3") (pintype "passive"))
    )
    (net (code "68") (name "unconnected-(Trimmpoti-CW-Pad3)") (class "Default")
      (node (ref "Trimmpoti") (pin "3") (pinfunction "CW_3") (pintype "passive"))
    )
  )
)
